# Top_Level.net
KiCad netlist of a schematic drawn in Altium Designer
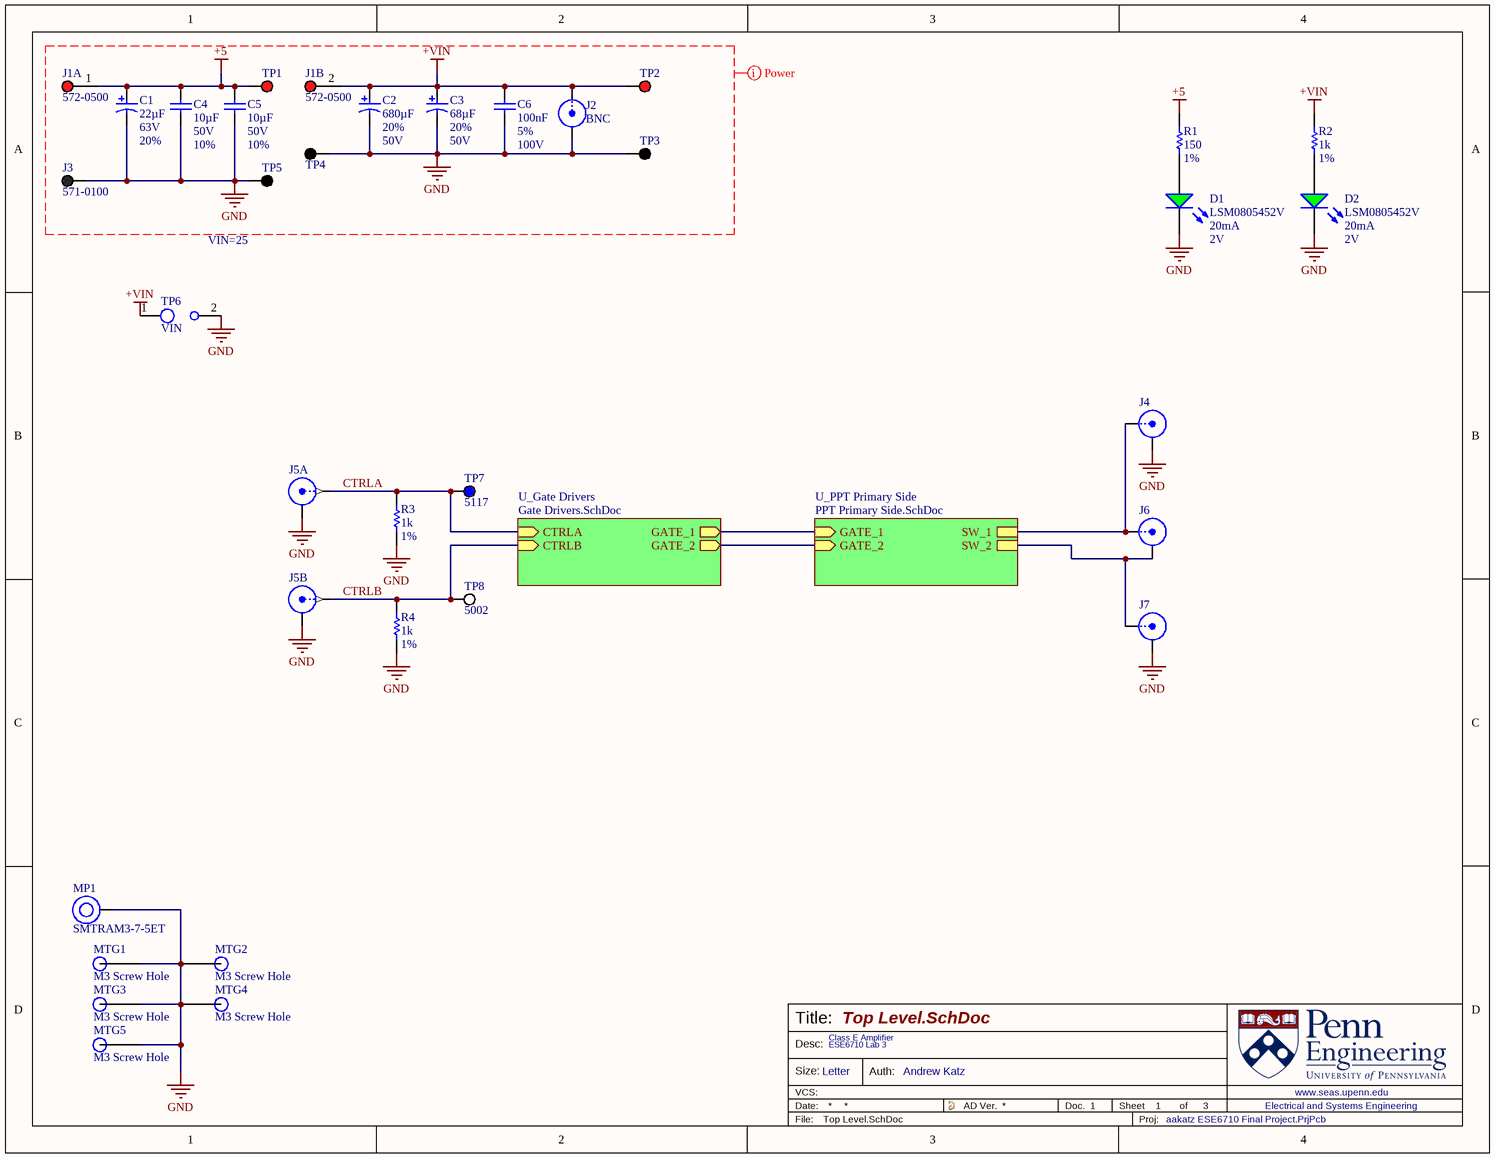
[diagram p0: Top Level.SchDoc]

(export (version "E")
  (design (tool "Eeschema 10.0.6"))
  (components
    (comp (ref "C1")
      (value "22µF")
      (footprint "CAPAE_D8H6_KEMET")
      (fields
        (field (name "VOLTAGE") "63V")
        (field (name "TOLERANCE") "20%")
        (field (name "Comment") "A768KE226M1JLAE054")
      )
      (libsource (lib "University of Pennsylvania (ESE)") (part "NIC-CAP-P-2"))
    )
    (comp (ref "C2")
      (value "680µF")
      (footprint "FP-RAD-TH-D_12_5_0_5-L_30-MFG")
      (fields
        (field (name "TOLERANCE") "20%")
        (field (name "VOLTAGE") "50V")
        (field (name "Comment") "EEU-FC1H681L")
      )
      (libsource (lib "University of Pennsylvania (ESE)") (part "NIC-CAP-P-2"))
    )
    (comp (ref "C3")
      (value "68µF")
      (footprint "FP-OS-CON-SMT-F12-MFG")
      (description "Cap Aluminum Polymer 68uF 50VDC 20%( 10 X 12.6mm) SMD 0.02 Ohm 4300mA 5000h 105C T/R")
      (fields
        (field (name "TOLERANCE") "20%")
        (field (name "VOLTAGE") "50V")
        (field (name "Comment") "50SVPF68M")
      )
      (libsource (lib "University of Pennsylvania (ESE)") (part "NIC-CAP-P-2"))
    )
    (comp (ref "C4")
      (value "10µF")
      (footprint "1206_CAP")
      (description "Capacitor Surface Mount 1206 Footprint 10UF 25V 10% Tolerance Ceramic X5R")
      (fields
        (field (name "VOLTAGE") "50V")
        (field (name "MANUFACTURER") "Various")
        (field (name "JLCPCB PART #") "C13585")
        (field (name "TOLERANCE") "10%")
      )
      (libsource (lib "University of Pennsylvania (ESE)") (part "cap"))
    )
    (comp (ref "C5")
      (value "10µF")
      (footprint "1206_CAP")
      (description "Capacitor Surface Mount 1206 Footprint 10UF 25V 10% Tolerance Ceramic X5R")
      (fields
        (field (name "VOLTAGE") "50V")
        (field (name "MANUFACTURER") "Various")
        (field (name "JLCPCB PART #") "C13585")
        (field (name "TOLERANCE") "10%")
      )
      (libsource (lib "University of Pennsylvania (ESE)") (part "cap"))
    )
    (comp (ref "C6")
      (value "100nF")
      (footprint "1206_CAP_75H_TDK")
      (description "100V 100nF C0G 卤5% 1206 Multilayer Ceramic Capacitors MLCC - SMD/SMT ROHS")
      (fields
        (field (name "TOLERANCE") "5%")
        (field (name "VOLTAGE") "100V")
        (field (name "Comment") "CAP 1206 0.1UF 100V 5% C0G")
      )
      (libsource (lib "University of Pennsylvania (ESE)") (part "cap"))
    )
    (comp (ref "D1")
      (value "LSM0805452V")
      (footprint "LED_0805")
      (description "Single Color LED, Green, 0805")
      (fields (field (name "CURRENT") "20mA") (field (name "FORWARD VOLTAGE") "2V"))
      (libsource (lib "University of Pennsylvania (ESE)") (part "LED-GREEN-AK-2"))
    )
    (comp (ref "D2")
      (value "LSM0805452V")
      (footprint "LED_0805")
      (description "Single Color LED, Green, 0805")
      (fields (field (name "CURRENT") "20mA") (field (name "FORWARD VOLTAGE") "2V"))
      (libsource (lib "University of Pennsylvania (ESE)") (part "LED-GREEN-AK-2"))
    )
    (comp (ref "J1")
      (value "572-0500")
      (footprint "572-0500-Footprint-1")
      (description "Banana Jack, Red, Dual, 50V (Working), 10A, 1.94MM Rohs Compliant: Yes")
      (libsource (lib "University of Pennsylvania (ESE)") (part "572-0500"))
    )
    (comp (ref "J2")
      (value "BNC")
      (footprint "112404-Footprint-1")
      (description "BNC Connector Jack, Female Socket 50 Ohms Through Hole Solder")
      (libsource (lib "") (part "RF Connector_1"))
    )
    (comp (ref "J3")
      (value "571-0100")
      (footprint "571-0100-Footprint-1")
      (description "Banana Jack, Black")
      (libsource (lib "University of Pennsylvania (ESE)") (part "571-0100"))
    )
    (comp (ref "J4")
      (value "CON-SMA-EDGE-S")
      (footprint "FP-SMA-J-P-H-ST-EM1-MFG")
      (description "Sma Female Connector Jack, Pcb Edge Mount Rohs Compliant: Yes")
      (libsource (lib "University of Pennsylvania (ESE)") (part "RF Connector"))
    )
    (comp (ref "J5")
      (value "031-6575")
      (footprint "031-6575-Footprint-1")
      (description "RF / Coaxial Connector, BNC Coaxial, Right Angle Jack, Through Hole Right Angle, 50 ohm")
      (libsource (lib "University of Pennsylvania (ESE)") (part "Isolated Dual BNC"))
    )
    (comp (ref "J6")
      (value "CON-SMA-EDGE-S")
      (footprint "FP-SMA-J-P-H-ST-EM1-MFG")
      (description "Sma Female Connector Jack, Pcb Edge Mount Rohs Compliant: Yes")
      (libsource (lib "University of Pennsylvania (ESE)") (part "RF Connector"))
    )
    (comp (ref "J7")
      (value "CON-SMA-EDGE-S")
      (footprint "FP-SMA-J-P-H-ST-EM1-MFG")
      (description "Sma Female Connector Jack, Pcb Edge Mount Rohs Compliant: Yes")
      (libsource (lib "University of Pennsylvania (ESE)") (part "RF Connector"))
    )
    (comp (ref "MP1")
      (value "SMTRAM3-7-5ET")
      (footprint "SMTRAM3-7-5ET-Footprint-1")
      (description "Surface Mount Rangle M3 Electro-plated Tin")
      (libsource (lib "University of Pennsylvania (ESE)") (part "Spacer"))
    )
    (comp (ref "MTG1")
      (value "M3 Screw Hole")
      (footprint "M3 Screw Hole-Footprint-1")
      (description "Close clearance Fit for M3 Screw Hole; PCB Mounting for M3 Screw")
      (libsource (lib "University of Pennsylvania (ESE)") (part "M3 Screw Hole-Symbol-1"))
    )
    (comp (ref "MTG2")
      (value "M3 Screw Hole")
      (footprint "M3 Screw Hole-Footprint-1")
      (description "Close clearance Fit for M3 Screw Hole; PCB Mounting for M3 Screw")
      (libsource (lib "University of Pennsylvania (ESE)") (part "M3 Screw Hole-Symbol-1"))
    )
    (comp (ref "MTG3")
      (value "M3 Screw Hole")
      (footprint "M3 Screw Hole-Footprint-1")
      (description "Close clearance Fit for M3 Screw Hole; PCB Mounting for M3 Screw")
      (libsource (lib "University of Pennsylvania (ESE)") (part "M3 Screw Hole-Symbol-1"))
    )
    (comp (ref "MTG4")
      (value "M3 Screw Hole")
      (footprint "M3 Screw Hole-Footprint-1")
      (description "Close clearance Fit for M3 Screw Hole; PCB Mounting for M3 Screw")
      (libsource (lib "University of Pennsylvania (ESE)") (part "M3 Screw Hole-Symbol-1"))
    )
    (comp (ref "MTG5")
      (value "M3 Screw Hole")
      (footprint "M3 Screw Hole-Footprint-1")
      (description "Close clearance Fit for M3 Screw Hole; PCB Mounting for M3 Screw")
      (libsource (lib "University of Pennsylvania (ESE)") (part "M3 Screw Hole-Symbol-1"))
    )
    (comp (ref "R1")
      (value "150")
      (footprint "0805_RES")
      (description "Resistor Surface Mount, 150 Ohms, 0805 Footprint, 1% Tolerance 0.125W")
      (fields
        (field (name "MANUFACTURER") "Various")
        (field (name "TOLERANCE") "1%")
        (field (name "Comment") "RES 0805 150 1%")
      )
      (libsource (lib "University of Pennsylvania (ESE)") (part "res"))
    )
    (comp (ref "R2")
      (value "1k")
      (footprint "0805_RES")
      (description "Resistor Surface Mount, 1K Ohms, 0805 Footprint, 1% Tolerance 0.125W")
      (fields
        (field (name "JLCPCB PART #") "C17513")
        (field (name "MANUFACTURER") "Various")
        (field (name "TOLERANCE") "1%")
      )
      (libsource (lib "University of Pennsylvania (ESE)") (part "res"))
    )
    (comp (ref "R3")
      (value "1k")
      (footprint "0805_RES")
      (description "Resistor Surface Mount, 1K Ohms, 0805 Footprint, 1% Tolerance 0.125W")
      (fields
        (field (name "JLCPCB PART #") "C17513")
        (field (name "MANUFACTURER") "Various")
        (field (name "TOLERANCE") "1%")
      )
      (libsource (lib "University of Pennsylvania (ESE)") (part "res"))
    )
    (comp (ref "R4")
      (value "1k")
      (footprint "0805_RES")
      (description "Resistor Surface Mount, 1K Ohms, 0805 Footprint, 1% Tolerance 0.125W")
      (fields
        (field (name "JLCPCB PART #") "C17513")
        (field (name "MANUFACTURER") "Various")
        (field (name "TOLERANCE") "1%")
      )
      (libsource (lib "University of Pennsylvania (ESE)") (part "res"))
    )
    (comp (ref "TP1")
      (value "5280")
      (footprint "KSTN-5010_V")
      (libsource (lib "University of Pennsylvania (ESE)") (part "TESTPOINT_RED"))
    )
    (comp (ref "TP2")
      (value "5280")
      (footprint "KSTN-5010_V")
      (libsource (lib "University of Pennsylvania (ESE)") (part "TESTPOINT_RED"))
    )
    (comp (ref "TP3")
      (value "5281")
      (footprint "KSTN-5011_V")
      (description "Test Point, Black, Multipurpose PCB TEST POINT BLACK MULTIPURPOSE 5011 5281; Testpoint")
      (libsource (lib "University of Pennsylvania (ESE)") (part "TESTPOINT_BLACK"))
    )
    (comp (ref "TP4")
      (value "5281")
      (footprint "KSTN-5011_V")
      (description "Test Point, Black, Multipurpose PCB TEST POINT BLACK MULTIPURPOSE 5011 5281; Testpoint")
      (libsource (lib "University of Pennsylvania (ESE)") (part "TESTPOINT_BLACK"))
    )
    (comp (ref "TP5")
      (value "5281")
      (footprint "KSTN-5011_V")
      (description "Test Point, Black, Multipurpose PCB TEST POINT BLACK MULTIPURPOSE 5011 5281; Testpoint")
      (libsource (lib "University of Pennsylvania (ESE)") (part "TESTPOINT_BLACK"))
    )
    (comp (ref "TP6")
      (value "Test Point - Scope with Ground Spring (No Socket)")
      (footprint "No Silk Test Point - Scope with Ground Spring-Footprint-1")
      (fields (field (name "NETNAME") "VIN"))
      (libsource (lib "University of Pennsylvania (ESE)") (part "Test Pad with Ground (No BOM)"))
    )
    (comp (ref "TP7")
      (value "5117")
      (footprint "KSTN-5117")
      (description "Test Point, Blue, 1-Pin THD, RoHS, Bulk")
      (fields (field (name "MANUFACTURER") "KeystoneElectronics"))
      (libsource (lib "University of Pennsylvania (ESE)") (part "5117"))
    )
    (comp (ref "TP8")
      (value "5002")
      (footprint "KSTN-5002")
      (description "Test Point, White, 1-Pin THD, RoHS, Bulk")
      (fields (field (name "MANUFACTURER") "KeystoneElectronics"))
      (libsource (lib "University of Pennsylvania (ESE)") (part "5002"))
    )
  )
  (nets
    (net (code "1") (name "+5") (class "Default")
      (node (ref "C1") (pin "1") (pinfunction "1_1") (pintype "passive"))
      (node (ref "C4") (pin "1") (pinfunction "1_1") (pintype "passive"))
      (node (ref "C5") (pin "1") (pinfunction "1_1") (pintype "passive"))
      (node (ref "J1") (pin "1") (pintype "passive"))
      (node (ref "R1") (pin "2") (pinfunction "2_2") (pintype "passive"))
      (node (ref "TP1") (pin "1") (pinfunction "1_1") (pintype "passive"))
    )
    (net (code "2") (name "+VIN") (class "Default")
      (node (ref "C2") (pin "1") (pinfunction "1_1") (pintype "passive"))
      (node (ref "C3") (pin "1") (pinfunction "1_1") (pintype "passive"))
      (node (ref "C6") (pin "2") (pinfunction "2_2") (pintype "passive"))
      (node (ref "J1") (pin "2") (pintype "passive"))
      (node (ref "J2") (pin "1") (pinfunction "1_1") (pintype "passive"))
      (node (ref "R2") (pin "2") (pinfunction "2_2") (pintype "passive"))
      (node (ref "TP2") (pin "1") (pinfunction "1_1") (pintype "passive"))
      (node (ref "TP6") (pin "1") (pinfunction "Signal_1") (pintype "passive"))
    )
    (net (code "3") (name "/CTRLA") (class "Default")
      (node (ref "J5") (pin "1") (pinfunction "1_1") (pintype "output"))
      (node (ref "R3") (pin "2") (pinfunction "2_2") (pintype "passive"))
      (node (ref "TP7") (pin "1") (pintype "passive"))
    )
    (net (code "4") (name "/CTRLB") (class "Default")
      (node (ref "J5") (pin "3") (pinfunction "3_3") (pintype "passive"))
      (node (ref "R4") (pin "2") (pinfunction "2_2") (pintype "passive"))
      (node (ref "TP8") (pin "1") (pintype "passive"))
    )
    (net (code "7") (name "/SW_1") (class "Default")
      (node (ref "J4") (pin "1") (pinfunction "1_1") (pintype "passive"))
      (node (ref "J6") (pin "1") (pinfunction "1_1") (pintype "passive"))
    )
    (net (code "8") (name "/SW_2") (class "Default")
      (node (ref "J6") (pin "2") (pinfunction "SHELL_2") (pintype "passive"))
      (node (ref "J7") (pin "1") (pinfunction "1_1") (pintype "passive"))
    )
    (net (code "9") (name "GND") (class "Default")
      (node (ref "C1") (pin "2") (pinfunction "2_2") (pintype "passive"))
      (node (ref "C2") (pin "2") (pinfunction "2_2") (pintype "passive"))
      (node (ref "C3") (pin "2") (pinfunction "2_2") (pintype "passive"))
      (node (ref "C4") (pin "2") (pinfunction "2_2") (pintype "passive"))
      (node (ref "C5") (pin "2") (pinfunction "2_2") (pintype "passive"))
      (node (ref "C6") (pin "1") (pinfunction "1_1") (pintype "passive"))
      (node (ref "D1") (pin "K") (pinfunction "K_K") (pintype "passive"))
      (node (ref "D2") (pin "K") (pinfunction "K_K") (pintype "passive"))
      (node (ref "J2") (pin "2") (pinfunction "SHELL_2") (pintype "passive"))
      (node (ref "J3") (pin "1") (pintype "passive"))
      (node (ref "J4") (pin "2") (pinfunction "SHELL_2") (pintype "passive"))
      (node (ref "J5") (pin "2") (pinfunction "SHELL_2") (pintype "passive"))
      (node (ref "J5") (pin "4") (pinfunction "SHELL_4") (pintype "passive"))
      (node (ref "J7") (pin "2") (pinfunction "SHELL_2") (pintype "passive"))
      (node (ref "MP1") (pin "1") (pinfunction "1_1") (pintype "passive"))
      (node (ref "MTG1") (pin "1") (pinfunction "1_1") (pintype "passive"))
      (node (ref "MTG2") (pin "1") (pinfunction "1_1") (pintype "passive"))
      (node (ref "MTG3") (pin "1") (pinfunction "1_1") (pintype "passive"))
      (node (ref "MTG4") (pin "1") (pinfunction "1_1") (pintype "passive"))
      (node (ref "MTG5") (pin "1") (pinfunction "1_1") (pintype "passive"))
      (node (ref "R3") (pin "1") (pinfunction "1_1") (pintype "passive"))
      (node (ref "R4") (pin "1") (pinfunction "1_1") (pintype "passive"))
      (node (ref "TP3") (pin "1") (pinfunction "1_1") (pintype "passive"))
      (node (ref "TP4") (pin "1") (pinfunction "1_1") (pintype "passive"))
      (node (ref "TP5") (pin "1") (pinfunction "1_1") (pintype "passive"))
      (node (ref "TP6") (pin "2") (pinfunction "GND_2") (pintype "passive"))
    )
    (net (code "10") (name "Net-(D1-PadA)") (class "Default")
      (node (ref "D1") (pin "A") (pinfunction "A_A") (pintype "passive"))
      (node (ref "R1") (pin "1") (pinfunction "1_1") (pintype "passive"))
    )
    (net (code "11") (name "Net-(D2-PadA)") (class "Default")
      (node (ref "D2") (pin "A") (pinfunction "A_A") (pintype "passive"))
      (node (ref "R2") (pin "1") (pinfunction "1_1") (pintype "passive"))
    )
  )
)
